# DAU_Kupplung_3phasig_V1_3.net
KiCad netlist of a schematic drawn in EAGLE
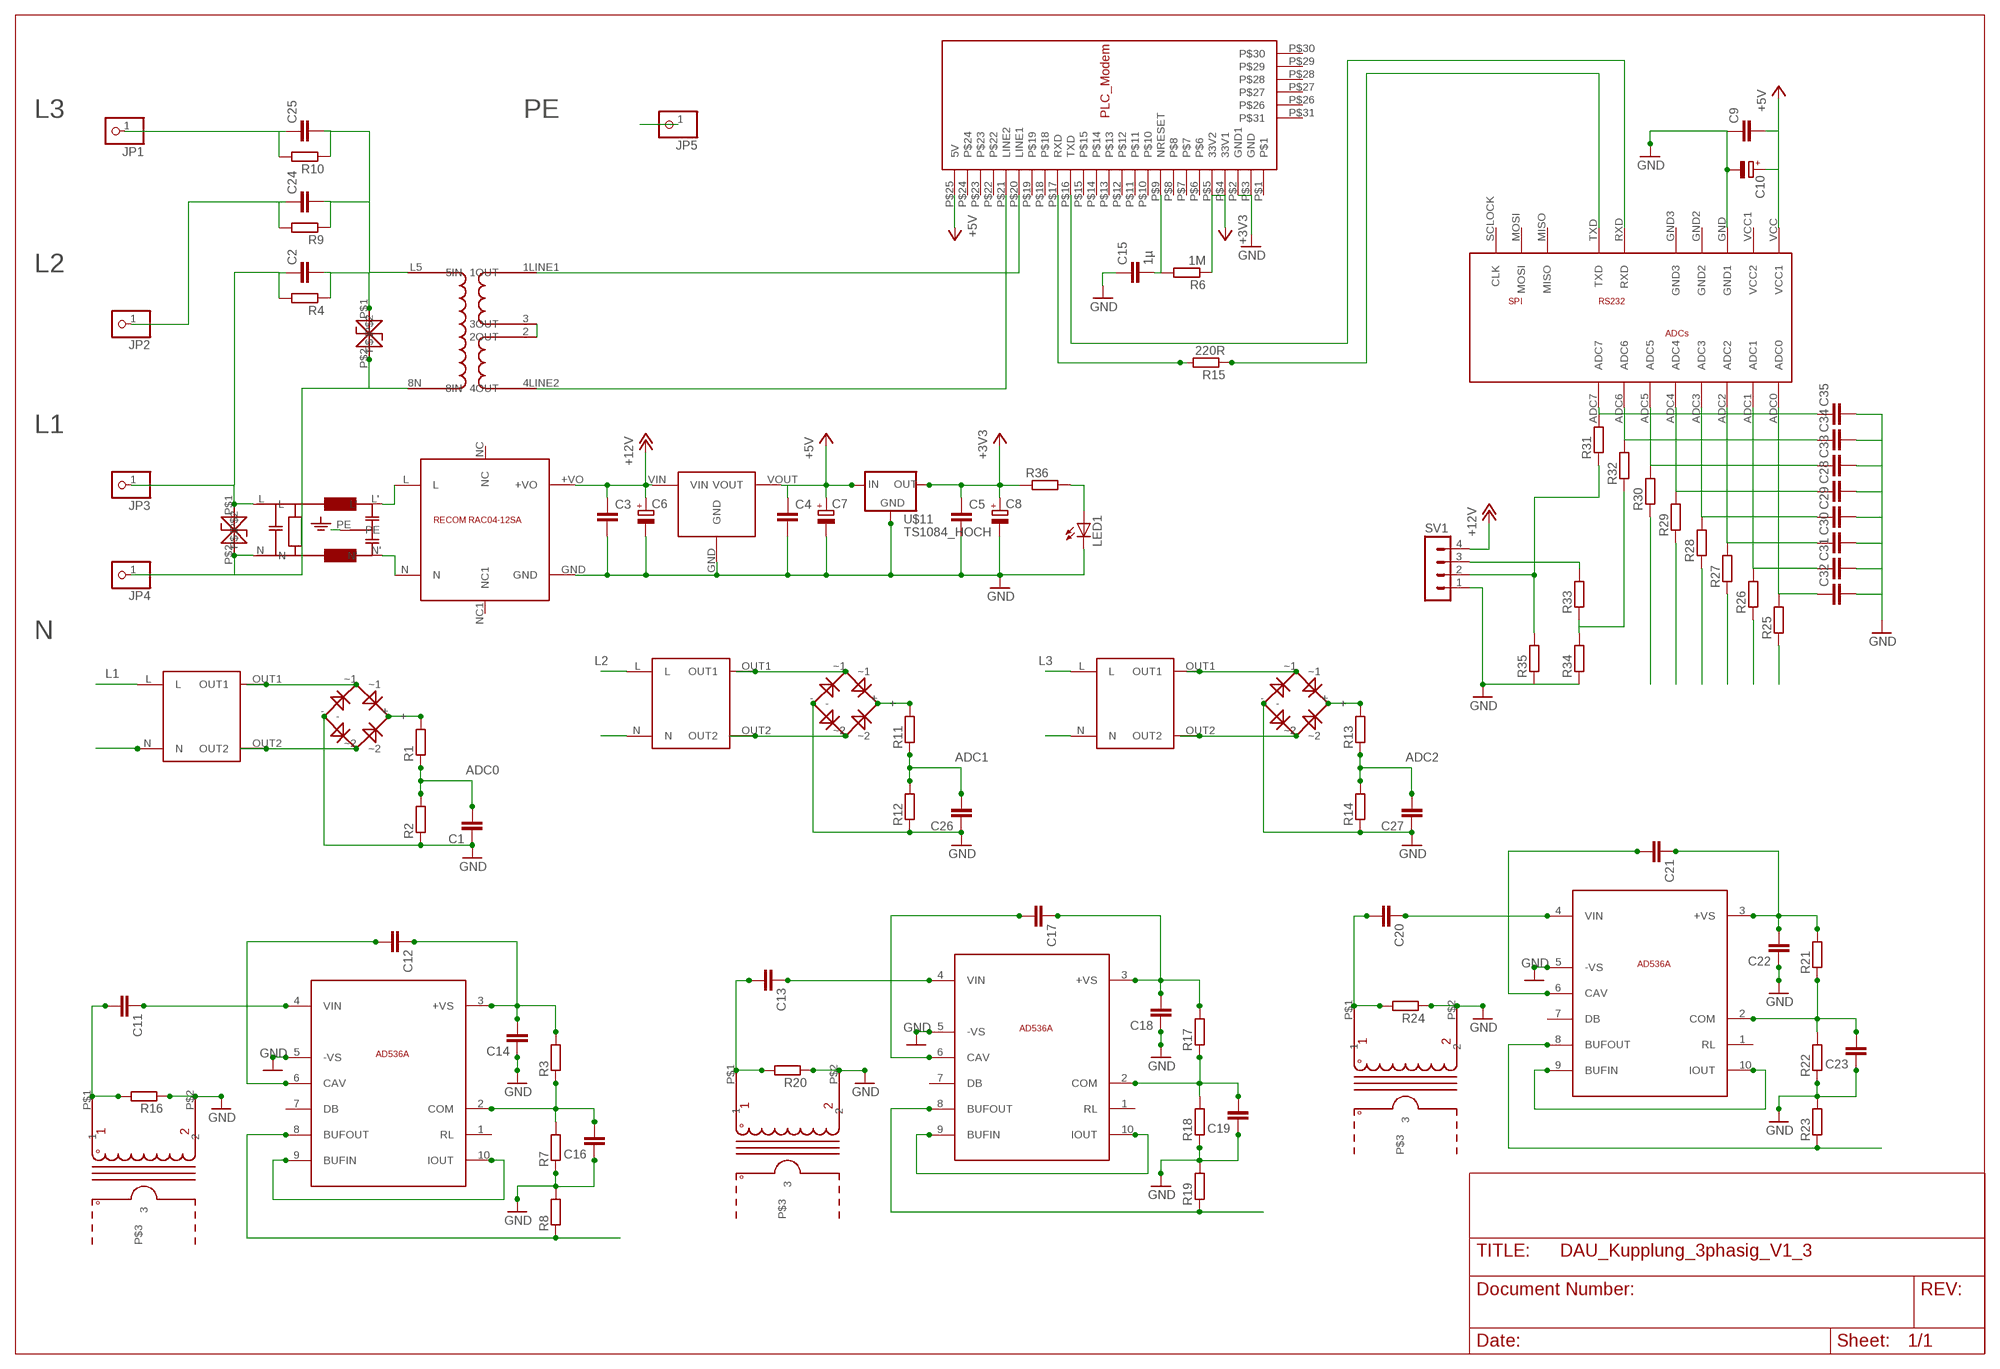
[diagram p0: schematic, sheet 1]

(export (version "E")
  (design (tool "Eeschema 10.0.6"))
  (components
    (comp (ref "C1")
      (value "C2,5-3")
      (footprint "eagle-import:C2.5-3")
      (libsource (lib "eagle-import") (part "C2,5-3"))
    )
    (comp (ref "C2")
      (value "C-EU225-087X268")
      (footprint "eagle-import:C225-087X268")
      (libsource (lib "eagle-import") (part "resistor_C-EU225-087X268"))
    )
    (comp (ref "C3")
      (value "C-EU025-040X050")
      (footprint "eagle-import:C025-040X050")
      (libsource (lib "eagle-import") (part "resistor_C-EU025-040X050"))
    )
    (comp (ref "C4")
      (value "C-EU025-040X050")
      (footprint "eagle-import:C025-040X050")
      (libsource (lib "eagle-import") (part "resistor_C-EU025-040X050"))
    )
    (comp (ref "C5")
      (value "C-EU025-040X050")
      (footprint "eagle-import:C025-040X050")
      (libsource (lib "eagle-import") (part "resistor_C-EU025-040X050"))
    )
    (comp (ref "C6")
      (value "CPOL-EUE2.5-6")
      (footprint "eagle-import:E2,5-6")
      (libsource (lib "eagle-import") (part "resistor_CPOL-EUE2.5-6"))
    )
    (comp (ref "C7")
      (value "CPOL-EUE2.5-6")
      (footprint "eagle-import:E2,5-6")
      (libsource (lib "eagle-import") (part "resistor_CPOL-EUE2.5-6"))
    )
    (comp (ref "C8")
      (value "CPOL-EUE2.5-6")
      (footprint "eagle-import:E2,5-6")
      (libsource (lib "eagle-import") (part "resistor_CPOL-EUE2.5-6"))
    )
    (comp (ref "C9")
      (value "C-EU025-040X050")
      (footprint "eagle-import:C025-040X050")
      (libsource (lib "eagle-import") (part "C-EU025-040X050"))
    )
    (comp (ref "C10")
      (value "CPOL-EUE2,5-6E")
      (footprint "eagle-import:E2,5-6E")
      (libsource (lib "eagle-import") (part "CPOL-EUE2,5-6E"))
    )
    (comp (ref "C11")
      (value "C2,5-3")
      (footprint "eagle-import:C2.5-3")
      (libsource (lib "eagle-import") (part "C2,5-3"))
    )
    (comp (ref "C12")
      (value "C2,5-3")
      (footprint "eagle-import:C2.5-3")
      (libsource (lib "eagle-import") (part "C2,5-3"))
    )
    (comp (ref "C13")
      (value "C2,5-3")
      (footprint "eagle-import:C2.5-3")
      (libsource (lib "eagle-import") (part "C2,5-3"))
    )
    (comp (ref "C14")
      (value "C2,5-3")
      (footprint "eagle-import:C2.5-3")
      (libsource (lib "eagle-import") (part "C2,5-3"))
    )
    (comp (ref "C15")
      (value "1µ")
      (footprint "eagle-import:C025-040X050")
      (libsource (lib "eagle-import") (part "resistor_C-EU025-040X050"))
    )
    (comp (ref "C16")
      (value "C2,5-3")
      (footprint "eagle-import:C2.5-3")
      (libsource (lib "eagle-import") (part "C2,5-3"))
    )
    (comp (ref "C17")
      (value "C2,5-3")
      (footprint "eagle-import:C2.5-3")
      (libsource (lib "eagle-import") (part "C2,5-3"))
    )
    (comp (ref "C18")
      (value "C2,5-3")
      (footprint "eagle-import:C2.5-3")
      (libsource (lib "eagle-import") (part "C2,5-3"))
    )
    (comp (ref "C19")
      (value "C2,5-3")
      (footprint "eagle-import:C2.5-3")
      (libsource (lib "eagle-import") (part "C2,5-3"))
    )
    (comp (ref "C20")
      (value "C2,5-3")
      (footprint "eagle-import:C2.5-3")
      (libsource (lib "eagle-import") (part "C2,5-3"))
    )
    (comp (ref "C21")
      (value "C2,5-3")
      (footprint "eagle-import:C2.5-3")
      (libsource (lib "eagle-import") (part "C2,5-3"))
    )
    (comp (ref "C22")
      (value "C2,5-3")
      (footprint "eagle-import:C2.5-3")
      (libsource (lib "eagle-import") (part "C2,5-3"))
    )
    (comp (ref "C23")
      (value "C2,5-3")
      (footprint "eagle-import:C2.5-3")
      (libsource (lib "eagle-import") (part "C2,5-3"))
    )
    (comp (ref "C24")
      (value "C-EU225-087X268")
      (footprint "eagle-import:C225-087X268")
      (libsource (lib "eagle-import") (part "resistor_C-EU225-087X268"))
    )
    (comp (ref "C25")
      (value "C-EU225-087X268")
      (footprint "eagle-import:C225-087X268")
      (libsource (lib "eagle-import") (part "resistor_C-EU225-087X268"))
    )
    (comp (ref "C26")
      (value "C2,5-3")
      (footprint "eagle-import:C2.5-3")
      (libsource (lib "eagle-import") (part "C2,5-3"))
    )
    (comp (ref "C27")
      (value "C2,5-3")
      (footprint "eagle-import:C2.5-3")
      (libsource (lib "eagle-import") (part "C2,5-3"))
    )
    (comp (ref "C28")
      (value "C-EUC0805K")
      (footprint "eagle-import:C0805K")
      (libsource (lib "eagle-import") (part "resistor_C-EUC0805K"))
    )
    (comp (ref "C29")
      (value "C-EUC0805K")
      (footprint "eagle-import:C0805K")
      (libsource (lib "eagle-import") (part "resistor_C-EUC0805K"))
    )
    (comp (ref "C30")
      (value "C-EUC0805K")
      (footprint "eagle-import:C0805K")
      (libsource (lib "eagle-import") (part "resistor_C-EUC0805K"))
    )
    (comp (ref "C31")
      (value "C-EUC0805K")
      (footprint "eagle-import:C0805K")
      (libsource (lib "eagle-import") (part "resistor_C-EUC0805K"))
    )
    (comp (ref "C32")
      (value "C-EUC0805K")
      (footprint "eagle-import:C0805K")
      (libsource (lib "eagle-import") (part "resistor_C-EUC0805K"))
    )
    (comp (ref "C33")
      (value "C-EUC0805K")
      (footprint "eagle-import:C0805K")
      (libsource (lib "eagle-import") (part "resistor_C-EUC0805K"))
    )
    (comp (ref "C34")
      (value "C-EUC0805K")
      (footprint "eagle-import:C0805K")
      (libsource (lib "eagle-import") (part "resistor_C-EUC0805K"))
    )
    (comp (ref "C35")
      (value "C-EUC0805K")
      (footprint "eagle-import:C0805K")
      (libsource (lib "eagle-import") (part "resistor_C-EUC0805K"))
    )
    (comp (ref "JP1")
      (value "PINHD-1X1")
      (footprint "eagle-import:1X01")
      (libsource (lib "eagle-import") (part "PINHD-1X1"))
    )
    (comp (ref "JP2")
      (value "PINHD-1X1")
      (footprint "eagle-import:1X01")
      (libsource (lib "eagle-import") (part "PINHD-1X1"))
    )
    (comp (ref "JP3")
      (value "PINHD-1X1")
      (footprint "eagle-import:1X01")
      (libsource (lib "eagle-import") (part "PINHD-1X1"))
    )
    (comp (ref "JP4")
      (value "PINHD-1X1")
      (footprint "eagle-import:1X01")
      (libsource (lib "eagle-import") (part "PINHD-1X1"))
    )
    (comp (ref "JP5")
      (value "PINHD-1X1")
      (footprint "eagle-import:1X01")
      (libsource (lib "eagle-import") (part "PINHD-1X1"))
    )
    (comp (ref "LED1")
      (value "LEDSQR2X5")
      (footprint "eagle-import:LED2X5")
      (libsource (lib "eagle-import") (part "LEDSQR2X5"))
    )
    (comp (ref "R1")
      (value "R-EU_0204/7")
      (footprint "eagle-import:0204_7")
      (libsource (lib "eagle-import") (part "R-EU_0204/7"))
    )
    (comp (ref "R2")
      (value "R-EU_0204/7")
      (footprint "eagle-import:0204_7")
      (libsource (lib "eagle-import") (part "R-EU_0204/7"))
    )
    (comp (ref "R3")
      (value "R-EU_0204/7")
      (footprint "eagle-import:0204_7")
      (libsource (lib "eagle-import") (part "R-EU_0204/7"))
    )
    (comp (ref "R4")
      (value "R-EU_0204/7")
      (footprint "eagle-import:0204_7")
      (libsource (lib "eagle-import") (part "R-EU_0204/7"))
    )
    (comp (ref "R6")
      (value "1M")
      (footprint "eagle-import:0204_7")
      (libsource (lib "eagle-import") (part "R-EU_0204/7"))
    )
    (comp (ref "R7")
      (value "R-EU_0204/7")
      (footprint "eagle-import:0204_7")
      (libsource (lib "eagle-import") (part "R-EU_0204/7"))
    )
    (comp (ref "R8")
      (value "R-EU_0204/7")
      (footprint "eagle-import:0204_7")
      (libsource (lib "eagle-import") (part "R-EU_0204/7"))
    )
    (comp (ref "R9")
      (value "R-EU_0204/7")
      (footprint "eagle-import:0204_7")
      (libsource (lib "eagle-import") (part "R-EU_0204/7"))
    )
    (comp (ref "R10")
      (value "R-EU_0204/7")
      (footprint "eagle-import:0204_7")
      (libsource (lib "eagle-import") (part "R-EU_0204/7"))
    )
    (comp (ref "R11")
      (value "R-EU_0204/7")
      (footprint "eagle-import:0204_7")
      (libsource (lib "eagle-import") (part "R-EU_0204/7"))
    )
    (comp (ref "R12")
      (value "R-EU_0204/7")
      (footprint "eagle-import:0204_7")
      (libsource (lib "eagle-import") (part "R-EU_0204/7"))
    )
    (comp (ref "R13")
      (value "R-EU_0204/7")
      (footprint "eagle-import:0204_7")
      (libsource (lib "eagle-import") (part "R-EU_0204/7"))
    )
    (comp (ref "R14")
      (value "R-EU_0204/7")
      (footprint "eagle-import:0204_7")
      (libsource (lib "eagle-import") (part "R-EU_0204/7"))
    )
    (comp (ref "R15")
      (value "220R")
      (footprint "eagle-import:0204_7")
      (libsource (lib "eagle-import") (part "R-EU_0204/7"))
    )
    (comp (ref "R16")
      (value "R-EU_0204/7")
      (footprint "eagle-import:0204_7")
      (libsource (lib "eagle-import") (part "R-EU_0204/7"))
    )
    (comp (ref "R17")
      (value "R-EU_0204/7")
      (footprint "eagle-import:0204_7")
      (libsource (lib "eagle-import") (part "R-EU_0204/7"))
    )
    (comp (ref "R18")
      (value "R-EU_0204/7")
      (footprint "eagle-import:0204_7")
      (libsource (lib "eagle-import") (part "R-EU_0204/7"))
    )
    (comp (ref "R19")
      (value "R-EU_0204/7")
      (footprint "eagle-import:0204_7")
      (libsource (lib "eagle-import") (part "R-EU_0204/7"))
    )
    (comp (ref "R20")
      (value "R-EU_0204/7")
      (footprint "eagle-import:0204_7")
      (libsource (lib "eagle-import") (part "R-EU_0204/7"))
    )
    (comp (ref "R21")
      (value "R-EU_0204/7")
      (footprint "eagle-import:0204_7")
      (libsource (lib "eagle-import") (part "R-EU_0204/7"))
    )
    (comp (ref "R22")
      (value "R-EU_0204/7")
      (footprint "eagle-import:0204_7")
      (libsource (lib "eagle-import") (part "R-EU_0204/7"))
    )
    (comp (ref "R23")
      (value "R-EU_0204/7")
      (footprint "eagle-import:0204_7")
      (libsource (lib "eagle-import") (part "R-EU_0204/7"))
    )
    (comp (ref "R24")
      (value "R-EU_0204/7")
      (footprint "eagle-import:0204_7")
      (libsource (lib "eagle-import") (part "R-EU_0204/7"))
    )
    (comp (ref "R25")
      (value "R-EU_R0805")
      (footprint "eagle-import:R0805")
      (libsource (lib "eagle-import") (part "R-EU_R0805"))
    )
    (comp (ref "R26")
      (value "R-EU_R0805")
      (footprint "eagle-import:R0805")
      (libsource (lib "eagle-import") (part "R-EU_R0805"))
    )
    (comp (ref "R27")
      (value "R-EU_R0805")
      (footprint "eagle-import:R0805")
      (libsource (lib "eagle-import") (part "R-EU_R0805"))
    )
    (comp (ref "R28")
      (value "R-EU_R0805")
      (footprint "eagle-import:R0805")
      (libsource (lib "eagle-import") (part "R-EU_R0805"))
    )
    (comp (ref "R29")
      (value "R-EU_R0805")
      (footprint "eagle-import:R0805")
      (libsource (lib "eagle-import") (part "R-EU_R0805"))
    )
    (comp (ref "R30")
      (value "R-EU_R0805")
      (footprint "eagle-import:R0805")
      (libsource (lib "eagle-import") (part "R-EU_R0805"))
    )
    (comp (ref "R31")
      (value "R-EU_R0805")
      (footprint "eagle-import:R0805")
      (libsource (lib "eagle-import") (part "R-EU_R0805"))
    )
    (comp (ref "R32")
      (value "R-EU_R0805")
      (footprint "eagle-import:R0805")
      (libsource (lib "eagle-import") (part "R-EU_R0805"))
    )
    (comp (ref "R33")
      (value "R-EU_R0805")
      (footprint "eagle-import:R0805")
      (libsource (lib "eagle-import") (part "R-EU_R0805"))
    )
    (comp (ref "R34")
      (value "R-EU_R0805")
      (footprint "eagle-import:R0805")
      (libsource (lib "eagle-import") (part "R-EU_R0805"))
    )
    (comp (ref "R35")
      (value "R-EU_R0805")
      (footprint "eagle-import:R0805")
      (libsource (lib "eagle-import") (part "R-EU_R0805"))
    )
    (comp (ref "R36")
      (value "R-EU_R0805")
      (footprint "eagle-import:R0805")
      (libsource (lib "eagle-import") (part "R-EU_R0805"))
    )
    (comp (ref "SV1")
      (value "MA04-1")
      (footprint "eagle-import:MA04-1")
      (libsource (lib "eagle-import") (part "MA04-1"))
    )
    (comp (ref "TSV1")
      (value "TSV")
      (footprint "eagle-import:TSV")
      (libsource (lib "eagle-import") (part "TSV"))
    )
    (comp (ref "TSV2")
      (value "TSV")
      (footprint "eagle-import:TSV")
      (libsource (lib "eagle-import") (part "TSV"))
    )
    (comp (ref "U$1")
      (value "RECOM_RAC04_12SA")
      (footprint "eagle-import:RAC04_12SA")
      (libsource (lib "eagle-import") (part "RECOM_RAC04_12SA"))
    )
    (comp (ref "U$2")
      (value "SICHERHEITSTRAFO")
      (footprint "eagle-import:TRAFO_0,35VA")
      (libsource (lib "eagle-import") (part "SICHERHEITSTRAFO"))
    )
    (comp (ref "U$3")
      (value "ADUC831_MINIMUM")
      (footprint "eagle-import:ADUC_MINIMUM")
      (libsource (lib "eagle-import") (part "ADUC831_MINIMUM"))
    )
    (comp (ref "U$4")
      (value "MODEMSTECKER")
      (footprint "eagle-import:MODEM_FUSS")
      (libsource (lib "eagle-import") (part "MODEMSTECKER"))
    )
    (comp (ref "U$5")
      (value "PLC_UEBERTRAGER_V2")
      (footprint "eagle-import:PLC-UEBERTRAGER_V2")
      (libsource (lib "eagle-import") (part "PLC_UEBERTRAGER_V2"))
    )
    (comp (ref "U$6")
      (value "AC1010")
      (footprint "eagle-import:AC1010")
      (libsource (lib "eagle-import") (part "AC1010"))
    )
    (comp (ref "U$7")
      (value "AC1010")
      (footprint "eagle-import:AC1010")
      (libsource (lib "eagle-import") (part "AC1010"))
    )
    (comp (ref "U$8")
      (value "RECTIFIER")
      (footprint "eagle-import:RECTIFIER")
      (libsource (lib "eagle-import") (part "RECTIFIER"))
    )
    (comp (ref "U$10")
      (value "RECOM_785_05")
      (footprint "eagle-import:RECOM785X")
      (libsource (lib "eagle-import") (part "RECOM_785_05"))
    )
    (comp (ref "U$11")
      (value "TS1084_HOCH")
      (footprint "eagle-import:TS1084_HOCH")
      (libsource (lib "eagle-import") (part "TS1084_HOCH"))
    )
    (comp (ref "U$12")
      (value "AD536")
      (footprint "eagle-import:TO100_10PIN")
      (libsource (lib "eagle-import") (part "AD536"))
    )
    (comp (ref "U$13")
      (value "AD536")
      (footprint "eagle-import:TO100_10PIN")
      (libsource (lib "eagle-import") (part "AD536"))
    )
    (comp (ref "U$14")
      (value "AC1010")
      (footprint "eagle-import:AC1010")
      (libsource (lib "eagle-import") (part "AC1010"))
    )
    (comp (ref "U$15")
      (value "AD536")
      (footprint "eagle-import:TO100_10PIN")
      (libsource (lib "eagle-import") (part "AD536"))
    )
    (comp (ref "U$16")
      (value "SICHERHEITSTRAFO")
      (footprint "eagle-import:TRAFO_0,35VA")
      (libsource (lib "eagle-import") (part "SICHERHEITSTRAFO"))
    )
    (comp (ref "U$17")
      (value "RECTIFIER")
      (footprint "eagle-import:RECTIFIER")
      (libsource (lib "eagle-import") (part "RECTIFIER"))
    )
    (comp (ref "U$18")
      (value "SICHERHEITSTRAFO")
      (footprint "eagle-import:TRAFO_0,35VA")
      (libsource (lib "eagle-import") (part "SICHERHEITSTRAFO"))
    )
    (comp (ref "U$19")
      (value "RECTIFIER")
      (footprint "eagle-import:RECTIFIER")
      (libsource (lib "eagle-import") (part "RECTIFIER"))
    )
    (comp (ref "U$20")
      (value "NETZFILTER_05_A")
      (footprint "eagle-import:NETZFILTER")
      (libsource (lib "eagle-import") (part "NETZFILTER_05_A"))
    )
  )
  (nets
    (net (code "1") (name "+3V3") (class "Default")
      (node (ref "C5") (pin "1") (pinfunction "1_1") (pintype "passive"))
      (node (ref "C8") (pin "+") (pinfunction "+_+") (pintype "passive"))
      (node (ref "R36") (pin "1") (pinfunction "1_1") (pintype "passive"))
      (node (ref "R6") (pin "1") (pinfunction "1_1") (pintype "passive"))
      (node (ref "U$11") (pin "OUT") (pinfunction "OUT_OUT") (pintype "passive"))
      (node (ref "U$4") (pin "P$4") (pinfunction "33V1_P$4") (pintype "bidirectional"))
      (node (ref "U$4") (pin "P$5") (pinfunction "33V2_P$5") (pintype "bidirectional"))
    )
    (net (code "2") (name "+5V") (class "Default")
      (node (ref "C10") (pin "+") (pinfunction "+_+") (pintype "passive"))
      (node (ref "C4") (pin "1") (pinfunction "1_1") (pintype "passive"))
      (node (ref "C7") (pin "+") (pinfunction "+_+") (pintype "passive"))
      (node (ref "C9") (pin "2") (pinfunction "2_2") (pintype "passive"))
      (node (ref "U$10") (pin "VOUT") (pinfunction "VOUT_VOUT") (pintype "bidirectional"))
      (node (ref "U$11") (pin "IN") (pinfunction "IN_IN") (pintype "input"))
      (node (ref "U$3") (pin "VCC") (pinfunction "VCC1_VCC") (pintype "bidirectional"))
      (node (ref "U$4") (pin "P$25") (pinfunction "5V_P$25") (pintype "bidirectional"))
    )
    (net (code "3") (name "+12V") (class "Default")
      (node (ref "C3") (pin "1") (pinfunction "1_1") (pintype "passive"))
      (node (ref "C6") (pin "+") (pinfunction "+_+") (pintype "passive"))
      (node (ref "SV1") (pin "4") (pinfunction "4_4") (pintype "passive"))
      (node (ref "U$1") (pin "+VO") (pinfunction "+VO_+VO") (pintype "bidirectional"))
      (node (ref "U$10") (pin "VIN") (pinfunction "VIN_VIN") (pintype "bidirectional"))
    )
    (net (code "4") (name "/I1") (class "Default")
      (node (ref "R28") (pin "1") (pinfunction "1_1") (pintype "passive"))
      (node (ref "R8") (pin "1") (pinfunction "1_1") (pintype "passive"))
      (node (ref "U$13") (pin "8") (pinfunction "BUFOUT_8") (pintype "bidirectional"))
    )
    (net (code "5") (name "/I2") (class "Default")
      (node (ref "R19") (pin "1") (pinfunction "1_1") (pintype "passive"))
      (node (ref "R29") (pin "1") (pinfunction "1_1") (pintype "passive"))
      (node (ref "U$12") (pin "8") (pinfunction "BUFOUT_8") (pintype "bidirectional"))
    )
    (net (code "6") (name "/I3") (class "Default")
      (node (ref "R23") (pin "1") (pinfunction "1_1") (pintype "passive"))
      (node (ref "R30") (pin "1") (pinfunction "1_1") (pintype "passive"))
      (node (ref "U$15") (pin "8") (pinfunction "BUFOUT_8") (pintype "bidirectional"))
    )
    (net (code "7") (name "/L1") (class "Default")
      (node (ref "C2") (pin "1") (pinfunction "1_1") (pintype "passive"))
      (node (ref "JP3") (pin "1") (pinfunction "1_1") (pintype "passive"))
      (node (ref "R4") (pin "2") (pinfunction "2_2") (pintype "passive"))
      (node (ref "TSV1") (pin "P$1") (pinfunction "P$1_P$1") (pintype "bidirectional"))
      (node (ref "U$2") (pin "L") (pinfunction "L_L") (pintype "bidirectional"))
      (node (ref "U$20") (pin "L") (pinfunction "L_L") (pintype "bidirectional"))
    )
    (net (code "8") (name "/L2") (class "Default")
      (node (ref "C24") (pin "1") (pinfunction "1_1") (pintype "passive"))
      (node (ref "JP2") (pin "1") (pinfunction "1_1") (pintype "passive"))
      (node (ref "R9") (pin "2") (pinfunction "2_2") (pintype "passive"))
      (node (ref "U$16") (pin "L") (pinfunction "L_L") (pintype "bidirectional"))
    )
    (net (code "9") (name "/L3") (class "Default")
      (node (ref "C25") (pin "1") (pinfunction "1_1") (pintype "passive"))
      (node (ref "JP1") (pin "1") (pinfunction "1_1") (pintype "passive"))
      (node (ref "R10") (pin "2") (pinfunction "2_2") (pintype "passive"))
      (node (ref "U$18") (pin "L") (pinfunction "L_L") (pintype "bidirectional"))
    )
    (net (code "10") (name "/N") (class "Default")
      (node (ref "JP4") (pin "1") (pinfunction "1_1") (pintype "passive"))
      (node (ref "TSV1") (pin "P$2") (pinfunction "P$2_P$2") (pintype "bidirectional"))
      (node (ref "TSV2") (pin "P$2") (pinfunction "P$2_P$2") (pintype "bidirectional"))
      (node (ref "U$16") (pin "N") (pinfunction "N_N") (pintype "bidirectional"))
      (node (ref "U$18") (pin "N") (pinfunction "N_N") (pintype "bidirectional"))
      (node (ref "U$2") (pin "N") (pinfunction "N_N") (pintype "bidirectional"))
      (node (ref "U$20") (pin "N") (pinfunction "N_N") (pintype "bidirectional"))
      (node (ref "U$5") (pin "8N") (pinfunction "8IN_8N") (pintype "input"))
    )
    (net (code "11") (name "/PE") (class "Default")
      (node (ref "JP5") (pin "1") (pinfunction "1_1") (pintype "passive"))
      (node (ref "U$20") (pin "PE") (pinfunction "PE_PE") (pintype "input"))
    )
    (net (code "12") (name "/U1") (class "Default")
      (node (ref "C1") (pin "2") (pinfunction "2_2") (pintype "passive"))
      (node (ref "R1") (pin "1") (pinfunction "1_1") (pintype "passive"))
      (node (ref "R2") (pin "2") (pinfunction "2_2") (pintype "passive"))
      (node (ref "R25") (pin "1") (pinfunction "1_1") (pintype "passive"))
    )
    (net (code "13") (name "/U2") (class "Default")
      (node (ref "C26") (pin "2") (pinfunction "2_2") (pintype "passive"))
      (node (ref "R11") (pin "1") (pinfunction "1_1") (pintype "passive"))
      (node (ref "R12") (pin "2") (pinfunction "2_2") (pintype "passive"))
      (node (ref "R26") (pin "1") (pinfunction "1_1") (pintype "passive"))
    )
    (net (code "14") (name "/U3") (class "Default")
      (node (ref "C27") (pin "2") (pinfunction "2_2") (pintype "passive"))
      (node (ref "R13") (pin "1") (pinfunction "1_1") (pintype "passive"))
      (node (ref "R14") (pin "2") (pinfunction "2_2") (pintype "passive"))
      (node (ref "R27") (pin "1") (pinfunction "1_1") (pintype "passive"))
    )
    (net (code "15") (name "GND") (class "Default")
      (node (ref "C1") (pin "1") (pinfunction "1_1") (pintype "passive"))
      (node (ref "C10") (pin "-") (pinfunction "-_-") (pintype "passive"))
      (node (ref "C14") (pin "1") (pinfunction "1_1") (pintype "passive"))
      (node (ref "C15") (pin "1") (pinfunction "1_1") (pintype "passive"))
      (node (ref "C16") (pin "1") (pinfunction "1_1") (pintype "passive"))
      (node (ref "C18") (pin "1") (pinfunction "1_1") (pintype "passive"))
      (node (ref "C19") (pin "1") (pinfunction "1_1") (pintype "passive"))
      (node (ref "C22") (pin "1") (pinfunction "1_1") (pintype "passive"))
      (node (ref "C23") (pin "1") (pinfunction "1_1") (pintype "passive"))
      (node (ref "C26") (pin "1") (pinfunction "1_1") (pintype "passive"))
      (node (ref "C27") (pin "1") (pinfunction "1_1") (pintype "passive"))
      (node (ref "C28") (pin "2") (pinfunction "2_2") (pintype "passive"))
      (node (ref "C29") (pin "2") (pinfunction "2_2") (pintype "passive"))
      (node (ref "C3") (pin "2") (pinfunction "2_2") (pintype "passive"))
      (node (ref "C30") (pin "2") (pinfunction "2_2") (pintype "passive"))
      (node (ref "C31") (pin "2") (pinfunction "2_2") (pintype "passive"))
      (node (ref "C32") (pin "2") (pinfunction "2_2") (pintype "passive"))
      (node (ref "C33") (pin "2") (pinfunction "2_2") (pintype "passive"))
      (node (ref "C34") (pin "2") (pinfunction "2_2") (pintype "passive"))
      (node (ref "C35") (pin "2") (pinfunction "2_2") (pintype "passive"))
      (node (ref "C4") (pin "2") (pinfunction "2_2") (pintype "passive"))
      (node (ref "C5") (pin "2") (pinfunction "2_2") (pintype "passive"))
      (node (ref "C6") (pin "-") (pinfunction "-_-") (pintype "passive"))
      (node (ref "C7") (pin "-") (pinfunction "-_-") (pintype "passive"))
      (node (ref "C8") (pin "-") (pinfunction "-_-") (pintype "passive"))
      (node (ref "C9") (pin "1") (pinfunction "1_1") (pintype "passive"))
      (node (ref "LED1") (pin "K") (pinfunction "C_K") (pintype "passive"))
      (node (ref "R12") (pin "1") (pinfunction "1_1") (pintype "passive"))
      (node (ref "R14") (pin "1") (pinfunction "1_1") (pintype "passive"))
      (node (ref "R16") (pin "1") (pinfunction "1_1") (pintype "passive"))
      (node (ref "R18") (pin "1") (pinfunction "1_1") (pintype "passive"))
      (node (ref "R19") (pin "2") (pinfunction "2_2") (pintype "passive"))
      (node (ref "R2") (pin "1") (pinfunction "1_1") (pintype "passive"))
      (node (ref "R20") (pin "1") (pinfunction "1_1") (pintype "passive"))
      (node (ref "R22") (pin "1") (pinfunction "1_1") (pintype "passive"))
      (node (ref "R23") (pin "2") (pinfunction "2_2") (pintype "passive"))
      (node (ref "R24") (pin "1") (pinfunction "1_1") (pintype "passive"))
      (node (ref "R34") (pin "1") (pinfunction "1_1") (pintype "passive"))
      (node (ref "R35") (pin "1") (pinfunction "1_1") (pintype "passive"))
      (node (ref "R7") (pin "1") (pinfunction "1_1") (pintype "passive"))
      (node (ref "R8") (pin "2") (pinfunction "2_2") (pintype "passive"))
      (node (ref "SV1") (pin "1") (pinfunction "1_1") (pintype "passive"))
      (node (ref "U$1") (pin "GND") (pinfunction "GND_GND") (pintype "bidirectional"))
      (node (ref "U$10") (pin "GND") (pinfunction "GND_GND") (pintype "bidirectional"))
      (node (ref "U$11") (pin "GND") (pinfunction "GND_GND") (pintype "input"))
      (node (ref "U$12") (pin "5") (pinfunction "-VS_5") (pintype "bidirectional"))
      (node (ref "U$13") (pin "5") (pinfunction "-VS_5") (pintype "bidirectional"))
      (node (ref "U$14") (pin "P$2") (pinfunction "2_P$2") (pintype "output"))
      (node (ref "U$15") (pin "5") (pinfunction "-VS_5") (pintype "bidirectional"))
      (node (ref "U$17") (pin "-") (pinfunction "-_-") (pintype "bidirectional"))
      (node (ref "U$19") (pin "-") (pinfunction "-_-") (pintype "bidirectional"))
      (node (ref "U$3") (pin "GND") (pinfunction "GND1_GND") (pintype "bidirectional"))
      (node (ref "U$4") (pin "P$2") (pinfunction "GND1_P$2") (pintype "bidirectional"))
      (node (ref "U$4") (pin "P$3") (pinfunction "GND_P$3") (pintype "bidirectional"))
      (node (ref "U$6") (pin "P$2") (pinfunction "2_P$2") (pintype "output"))
      (node (ref "U$7") (pin "P$2") (pinfunction "2_P$2") (pintype "output"))
      (node (ref "U$8") (pin "-") (pinfunction "-_-") (pintype "bidirectional"))
    )
    (net (code "16") (name "Net-(C28-Pad1)") (class "Default")
      (node (ref "C28") (pin "1") (pinfunction "1_1") (pintype "passive"))
      (node (ref "R29") (pin "2") (pinfunction "2_2") (pintype "passive"))
      (node (ref "U$3") (pin "ADC4") (pinfunction "ADC4_ADC4") (pintype "bidirectional"))
    )
    (net (code "17") (name "Net-(C29-Pad1)") (class "Default")
      (node (ref "C29") (pin "1") (pinfunction "1_1") (pintype "passive"))
      (node (ref "R28") (pin "2") (pinfunction "2_2") (pintype "passive"))
      (node (ref "U$3") (pin "ADC3") (pinfunction "ADC3_ADC3") (pintype "bidirectional"))
    )
    (net (code "18") (name "Net-(C30-Pad1)") (class "Default")
      (node (ref "C30") (pin "1") (pinfunction "1_1") (pintype "passive"))
      (node (ref "R27") (pin "2") (pinfunction "2_2") (pintype "passive"))
      (node (ref "U$3") (pin "ADC2") (pinfunction "ADC2_ADC2") (pintype "bidirectional"))
    )
    (net (code "19") (name "Net-(C31-Pad1)") (class "Default")
      (node (ref "C31") (pin "1") (pinfunction "1_1") (pintype "passive"))
      (node (ref "R26") (pin "2") (pinfunction "2_2") (pintype "passive"))
      (node (ref "U$3") (pin "ADC1") (pinfunction "ADC1_ADC1") (pintype "bidirectional"))
    )
    (net (code "20") (name "Net-(C32-Pad1)") (class "Default")
      (node (ref "C32") (pin "1") (pinfunction "1_1") (pintype "passive"))
      (node (ref "R25") (pin "2") (pinfunction "2_2") (pintype "passive"))
      (node (ref "U$3") (pin "ADC0") (pinfunction "ADC0_ADC0") (pintype "bidirectional"))
    )
    (net (code "21") (name "Net-(C33-Pad1)") (class "Default")
      (node (ref "C33") (pin "1") (pinfunction "1_1") (pintype "passive"))
      (node (ref "R30") (pin "2") (pinfunction "2_2") (pintype "passive"))
      (node (ref "U$3") (pin "ADC5") (pinfunction "ADC5_ADC5") (pintype "bidirectional"))
    )
    (net (code "22") (name "Net-(C34-Pad1)") (class "Default")
      (node (ref "C34") (pin "1") (pinfunction "1_1") (pintype "passive"))
      (node (ref "R32") (pin "2") (pinfunction "2_2") (pintype "passive"))
      (node (ref "U$3") (pin "ADC6") (pinfunction "ADC6_ADC6") (pintype "bidirectional"))
    )
    (net (code "23") (name "Net-(C35-Pad1)") (class "Default")
      (node (ref "C35") (pin "1") (pinfunction "1_1") (pintype "passive"))
      (node (ref "R31") (pin "2") (pinfunction "2_2") (pintype "passive"))
      (node (ref "U$3") (pin "ADC7") (pinfunction "ADC7_ADC7") (pintype "bidirectional"))
    )
    (net (code "24") (name "Net-(LED1-PadA)") (class "Default")
      (node (ref "LED1") (pin "A") (pinfunction "A_A") (pintype "passive"))
      (node (ref "R36") (pin "2") (pinfunction "2_2") (pintype "passive"))
    )
    (net (code "25") (name "Net-(R1-Pad2)") (class "Default")
      (node (ref "R1") (pin "2") (pinfunction "2_2") (pintype "passive"))
      (node (ref "U$8") (pin "+") (pinfunction "+_+") (pintype "bidirectional"))
    )
    (net (code "26") (name "Net-(R11-Pad2)") (class "Default")
      (node (ref "R11") (pin "2") (pinfunction "2_2") (pintype "passive"))
      (node (ref "U$17") (pin "+") (pinfunction "+_+") (pintype "bidirectional"))
    )
    (net (code "27") (name "Net-(R13-Pad2)") (class "Default")
      (node (ref "R13") (pin "2") (pinfunction "2_2") (pintype "passive"))
      (node (ref "U$19") (pin "+") (pinfunction "+_+") (pintype "bidirectional"))
    )
    (net (code "28") (name "Net-(R15-Pad1)") (class "Default")
      (node (ref "R15") (pin "1") (pinfunction "1_1") (pintype "passive"))
      (node (ref "U$3") (pin "TXD") (pinfunction "TXD_TXD") (pintype "bidirectional"))
    )
    (net (code "29") (name "Net-(R31-Pad1)") (class "Default")
      (node (ref "R31") (pin "1") (pinfunction "1_1") (pintype "passive"))
      (node (ref "R35") (pin "2") (pinfunction "2_2") (pintype "passive"))
      (node (ref "SV1") (pin "2") (pinfunction "2_2") (pintype "passive"))
    )
    (net (code "30") (name "Net-(R32-Pad1)") (class "Default")
      (node (ref "R32") (pin "1") (pinfunction "1_1") (pintype "passive"))
      (node (ref "R33") (pin "1") (pinfunction "1_1") (pintype "passive"))
      (node (ref "R34") (pin "2") (pinfunction "2_2") (pintype "passive"))
    )
    (net (code "31") (name "Net-(R33-Pad2)") (class "Default")
      (node (ref "R33") (pin "2") (pinfunction "2_2") (pintype "passive"))
      (node (ref "SV1") (pin "3") (pinfunction "3_3") (pintype "passive"))
    )
    (net (code "32") (name "Net-(U$1-PadL)") (class "Default")
      (node (ref "U$1") (pin "L") (pinfunction "L_L") (pintype "bidirectional"))
      (node (ref "U$20") (pin "L'") (pinfunction "L'_L'") (pintype "bidirectional"))
    )
    (net (code "33") (name "Net-(U$1-PadN)") (class "Default")
      (node (ref "U$1") (pin "N") (pinfunction "N_N") (pintype "bidirectional"))
      (node (ref "U$20") (pin "N'") (pinfunction "N'_N'") (pintype "bidirectional"))
    )
    (net (code "34") (name "Net-(U$4-LINE1)") (class "Default")
      (node (ref "U$4") (pin "P$20") (pinfunction "LINE1_P$20") (pintype "bidirectional"))
      (node (ref "U$5") (pin "1LINE1") (pinfunction "1OUT_1LINE1") (pintype "output"))
    )
    (net (code "35") (name "Net-(U$4-LINE2)") (class "Default")
      (node (ref "U$4") (pin "P$21") (pinfunction "LINE2_P$21") (pintype "bidirectional"))
      (node (ref "U$5") (pin "4LINE2") (pinfunction "4OUT_4LINE2") (pintype "output"))
    )
    (net (code "36") (name "Net-(U$4-NRESET)") (class "Default")
      (node (ref "C15") (pin "2") (pinfunction "2_2") (pintype "passive"))
      (node (ref "R6") (pin "2") (pinfunction "2_2") (pintype "passive"))
      (node (ref "U$4") (pin "P$9") (pinfunction "NRESET_P$9") (pintype "bidirectional"))
    )
    (net (code "37") (name "Net-(U$4-RXD)") (class "Default")
      (node (ref "R15") (pin "2") (pinfunction "2_2") (pintype "passive"))
      (node (ref "U$4") (pin "P$17") (pinfunction "RXD_P$17") (pintype "bidirectional"))
    )
    (net (code "38") (name "Net-(U$4-TXD)") (class "Default")
      (node (ref "U$3") (pin "RXD") (pinfunction "RXD_RXD") (pintype "bidirectional"))
      (node (ref "U$4") (pin "P$16") (pinfunction "TXD_P$16") (pintype "bidirectional"))
    )
    (net (code "39") (name "Net-(U$5-2OUT)") (class "Default")
      (node (ref "U$5") (pin "2") (pinfunction "2OUT_2") (pintype "output"))
      (node (ref "U$5") (pin "3") (pinfunction "3OUT_3") (pintype "output"))
    )
    (net (code "40") (name "Net-(U$5-5IN)") (class "Default")
      (node (ref "C2") (pin "2") (pinfunction "2_2") (pintype "passive"))
      (node (ref "C24") (pin "2") (pinfunction "2_2") (pintype "passive"))
      (node (ref "C25") (pin "2") (pinfunction "2_2") (pintype "passive"))
      (node (ref "R10") (pin "1") (pinfunction "1_1") (pintype "passive"))
      (node (ref "R4") (pin "1") (pinfunction "1_1") (pintype "passive"))
      (node (ref "R9") (pin "1") (pinfunction "1_1") (pintype "passive"))
      (node (ref "TSV2") (pin "P$1") (pinfunction "P$1_P$1") (pintype "bidirectional"))
      (node (ref "U$5") (pin "L5") (pinfunction "5IN_L5") (pintype "input"))
    )
    (net (code "41") (name "Net-(U$6-1)") (class "Default")
      (node (ref "C11") (pin "2") (pinfunction "2_2") (pintype "passive"))
      (node (ref "R16") (pin "2") (pinfunction "2_2") (pintype "passive"))
      (node (ref "U$6") (pin "P$1") (pinfunction "1_P$1") (pintype "output"))
    )
    (net (code "42") (name "Net-(U$7-1)") (class "Default")
      (node (ref "C13") (pin "2") (pinfunction "2_2") (pintype "passive"))
      (node (ref "R20") (pin "2") (pinfunction "2_2") (pintype "passive"))
      (node (ref "U$7") (pin "P$1") (pinfunction "1_P$1") (pintype "output"))
    )
    (net (code "43") (name "Net-(U$8-~{1})") (class "Default")
      (node (ref "U$2") (pin "OUT1") (pinfunction "OUT1_OUT1") (pintype "bidirectional"))
      (node (ref "U$8") (pin "~1") (pinfunction "~{1}_~1") (pintype "bidirectional"))
    )
    (net (code "44") (name "Net-(U$8-~{2})") (class "Default")
      (node (ref "U$2") (pin "OUT2") (pinfunction "OUT2_OUT2") (pintype "bidirectional"))
      (node (ref "U$8") (pin "~2") (pinfunction "~{2}_~2") (pintype "bidirectional"))
    )
    (net (code "45") (name "Net-(U$12-+VS)") (class "Default")
      (node (ref "C17") (pin "1") (pinfunction "1_1") (pintype "passive"))
      (node (ref "C18") (pin "2") (pinfunction "2_2") (pintype "passive"))
      (node (ref "R17") (pin "2") (pinfunction "2_2") (pintype "passive"))
      (node (ref "U$12") (pin "3") (pinfunction "+VS_3") (pintype "bidirectional"))
    )
    (net (code "46") (name "Net-(U$12-BUFIN)") (class "Default")
      (node (ref "U$12") (pin "10") (pinfunction "IOUT_10") (pintype "bidirectional"))
      (node (ref "U$12") (pin "9") (pinfunction "BUFIN_9") (pintype "bidirectional"))
    )
    (net (code "47") (name "Net-(U$12-CAV)") (class "Default")
      (node (ref "C17") (pin "2") (pinfunction "2_2") (pintype "passive"))
      (node (ref "U$12") (pin "6") (pinfunction "CAV_6") (pintype "bidirectional"))
    )
    (net (code "48") (name "Net-(U$12-COM)") (class "Default")
      (node (ref "C19") (pin "2") (pinfunction "2_2") (pintype "passive"))
      (node (ref "R17") (pin "1") (pinfunction "1_1") (pintype "passive"))
      (node (ref "R18") (pin "2") (pinfunction "2_2") (pintype "passive"))
      (node (ref "U$12") (pin "2") (pinfunction "COM_2") (pintype "bidirectional"))
    )
    (net (code "49") (name "Net-(U$12-VIN)") (class "Default")
      (node (ref "C13") (pin "1") (pinfunction "1_1") (pintype "passive"))
      (node (ref "U$12") (pin "4") (pinfunction "VIN_4") (pintype "bidirectional"))
    )
    (net (code "50") (name "Net-(U$13-+VS)") (class "Default")
      (node (ref "C12") (pin "1") (pinfunction "1_1") (pintype "passive"))
      (node (ref "C14") (pin "2") (pinfunction "2_2") (pintype "passive"))
      (node (ref "R3") (pin "2") (pinfunction "2_2") (pintype "passive"))
      (node (ref "U$13") (pin "3") (pinfunction "+VS_3") (pintype "bidirectional"))
    )
    (net (code "51") (name "Net-(U$13-BUFIN)") (class "Default")
      (node (ref "U$13") (pin "10") (pinfunction "IOUT_10") (pintype "bidirectional"))
      (node (ref "U$13") (pin "9") (pinfunction "BUFIN_9") (pintype "bidirectional"))
    )
    (net (code "52") (name "Net-(U$13-CAV)") (class "Default")
      (node (ref "C12") (pin "2") (pinfunction "2_2") (pintype "passive"))
      (node (ref "U$13") (pin "6") (pinfunction "CAV_6") (pintype "bidirectional"))
    )
    (net (code "53") (name "Net-(U$13-COM)") (class "Default")
      (node (ref "C16") (pin "2") (pinfunction "2_2") (pintype "passive"))
      (node (ref "R3") (pin "1") (pinfunction "1_1") (pintype "passive"))
      (node (ref "R7") (pin "2") (pinfunction "2_2") (pintype "passive"))
      (node (ref "U$13") (pin "2") (pinfunction "COM_2") (pintype "bidirectional"))
    )
    (net (code "54") (name "Net-(U$13-VIN)") (class "Default")
      (node (ref "C11") (pin "1") (pinfunction "1_1") (pintype "passive"))
      (node (ref "U$13") (pin "4") (pinfunction "VIN_4") (pintype "bidirectional"))
    )
    (net (code "55") (name "Net-(U$14-1)") (class "Default")
      (node (ref "C20") (pin "2") (pinfunction "2_2") (pintype "passive"))
      (node (ref "R24") (pin "2") (pinfunction "2_2") (pintype "passive"))
      (node (ref "U$14") (pin "P$1") (pinfunction "1_P$1") (pintype "output"))
    )
    (net (code "56") (name "Net-(U$15-+VS)") (class "Default")
      (node (ref "C21") (pin "1") (pinfunction "1_1") (pintype "passive"))
      (node (ref "C22") (pin "2") (pinfunction "2_2") (pintype "passive"))
      (node (ref "R21") (pin "2") (pinfunction "2_2") (pintype "passive"))
      (node (ref "U$15") (pin "3") (pinfunction "+VS_3") (pintype "bidirectional"))
    )
    (net (code "57") (name "Net-(U$15-BUFIN)") (class "Default")
      (node (ref "U$15") (pin "10") (pinfunction "IOUT_10") (pintype "bidirectional"))
      (node (ref "U$15") (pin "9") (pinfunction "BUFIN_9") (pintype "bidirectional"))
    )
    (net (code "58") (name "Net-(U$15-CAV)") (class "Default")
      (node (ref "C21") (pin "2") (pinfunction "2_2") (pintype "passive"))
      (node (ref "U$15") (pin "6") (pinfunction "CAV_6") (pintype "bidirectional"))
    )
    (net (code "59") (name "Net-(U$15-COM)") (class "Default")
      (node (ref "C23") (pin "2") (pinfunction "2_2") (pintype "passive"))
      (node (ref "R21") (pin "1") (pinfunction "1_1") (pintype "passive"))
      (node (ref "R22") (pin "2") (pinfunction "2_2") (pintype "passive"))
      (node (ref "U$15") (pin "2") (pinfunction "COM_2") (pintype "bidirectional"))
    )
    (net (code "60") (name "Net-(U$15-VIN)") (class "Default")
      (node (ref "C20") (pin "1") (pinfunction "1_1") (pintype "passive"))
      (node (ref "U$15") (pin "4") (pinfunction "VIN_4") (pintype "bidirectional"))
    )
    (net (code "61") (name "Net-(U$17-~{1})") (class "Default")
      (node (ref "U$16") (pin "OUT1") (pinfunction "OUT1_OUT1") (pintype "bidirectional"))
      (node (ref "U$17") (pin "~1") (pinfunction "~{1}_~1") (pintype "bidirectional"))
    )
    (net (code "62") (name "Net-(U$17-~{2})") (class "Default")
      (node (ref "U$16") (pin "OUT2") (pinfunction "OUT2_OUT2") (pintype "bidirectional"))
      (node (ref "U$17") (pin "~2") (pinfunction "~{2}_~2") (pintype "bidirectional"))
    )
    (net (code "63") (name "Net-(U$19-~{1})") (class "Default")
      (node (ref "U$18") (pin "OUT1") (pinfunction "OUT1_OUT1") (pintype "bidirectional"))
      (node (ref "U$19") (pin "~1") (pinfunction "~{1}_~1") (pintype "bidirectional"))
    )
    (net (code "64") (name "Net-(U$19-~{2})") (class "Default")
      (node (ref "U$18") (pin "OUT2") (pinfunction "OUT2_OUT2") (pintype "bidirectional"))
      (node (ref "U$19") (pin "~2") (pinfunction "~{2}_~2") (pintype "bidirectional"))
    )
    (net (code "65") (name "unconnected-(U$1-PadNC)") (class "Default")
      (node (ref "U$1") (pin "NC") (pinfunction "NC_NC") (pintype "bidirectional"))
    )
    (net (code "66") (name "unconnected-(U$1-PadNC1)") (class "Default")
      (node (ref "U$1") (pin "NC1") (pinfunction "NC1_NC1") (pintype "bidirectional"))
    )
    (net (code "67") (name "unconnected-(U$3-CLK-PadSCLOCK)") (class "Default")
      (node (ref "U$3") (pin "SCLOCK") (pinfunction "CLK_SCLOCK") (pintype "bidirectional"))
    )
    (net (code "68") (name "unconnected-(U$3-PadGND2)") (class "Default")
      (node (ref "U$3") (pin "GND2") (pinfunction "GND2_GND2") (pintype "bidirectional"))
    )
    (net (code "69") (name "unconnected-(U$3-PadGND3)") (class "Default")
      (node (ref "U$3") (pin "GND3") (pinfunction "GND3_GND3") (pintype "bidirectional"))
    )
    (net (code "70") (name "unconnected-(U$3-PadMISO)") (class "Default")
      (node (ref "U$3") (pin "MISO") (pinfunction "MISO_MISO") (pintype "bidirectional"))
    )
    (net (code "71") (name "unconnected-(U$3-PadMOSI)") (class "Default")
      (node (ref "U$3") (pin "MOSI") (pinfunction "MOSI_MOSI") (pintype "bidirectional"))
    )
    (net (code "72") (name "unconnected-(U$3-VCC2-PadVCC1)") (class "Default")
      (node (ref "U$3") (pin "VCC1") (pinfunction "VCC2_VCC1") (pintype "bidirectional"))
    )
    (net (code "73") (name "unconnected-(U$4-PadP$1)") (class "Default")
      (node (ref "U$4") (pin "P$1") (pinfunction "P$1_P$1") (pintype "bidirectional"))
    )
    (net (code "74") (name "unconnected-(U$4-PadP$6)") (class "Default")
      (node (ref "U$4") (pin "P$6") (pinfunction "P$6_P$6") (pintype "bidirectional"))
    )
    (net (code "75") (name "unconnected-(U$4-PadP$7)") (class "Default")
      (node (ref "U$4") (pin "P$7") (pinfunction "P$7_P$7") (pintype "bidirectional"))
    )
    (net (code "76") (name "unconnected-(U$4-PadP$8)") (class "Default")
      (node (ref "U$4") (pin "P$8") (pinfunction "P$8_P$8") (pintype "bidirectional"))
    )
    (net (code "77") (name "unconnected-(U$4-PadP$10)") (class "Default")
      (node (ref "U$4") (pin "P$10") (pinfunction "P$10_P$10") (pintype "bidirectional"))
    )
    (net (code "78") (name "unconnected-(U$4-PadP$11)") (class "Default")
      (node (ref "U$4") (pin "P$11") (pinfunction "P$11_P$11") (pintype "bidirectional"))
    )
    (net (code "79") (name "unconnected-(U$4-PadP$12)") (class "Default")
      (node (ref "U$4") (pin "P$12") (pinfunction "P$12_P$12") (pintype "bidirectional"))
    )
    (net (code "80") (name "unconnected-(U$4-PadP$13)") (class "Default")
      (node (ref "U$4") (pin "P$13") (pinfunction "P$13_P$13") (pintype "bidirectional"))
    )
    (net (code "81") (name "unconnected-(U$4-PadP$14)") (class "Default")
      (node (ref "U$4") (pin "P$14") (pinfunction "P$14_P$14") (pintype "bidirectional"))
    )
    (net (code "82") (name "unconnected-(U$4-PadP$15)") (class "Default")
      (node (ref "U$4") (pin "P$15") (pinfunction "P$15_P$15") (pintype "bidirectional"))
    )
    (net (code "83") (name "unconnected-(U$4-PadP$18)") (class "Default")
      (node (ref "U$4") (pin "P$18") (pinfunction "P$18_P$18") (pintype "bidirectional"))
    )
    (net (code "84") (name "unconnected-(U$4-PadP$19)") (class "Default")
      (node (ref "U$4") (pin "P$19") (pinfunction "P$19_P$19") (pintype "bidirectional"))
    )
    (net (code "85") (name "unconnected-(U$4-PadP$22)") (class "Default")
      (node (ref "U$4") (pin "P$22") (pinfunction "P$22_P$22") (pintype "bidirectional"))
    )
    (net (code "86") (name "unconnected-(U$4-PadP$23)") (class "Default")
      (node (ref "U$4") (pin "P$23") (pinfunction "P$23_P$23") (pintype "bidirectional"))
    )
    (net (code "87") (name "unconnected-(U$4-PadP$24)") (class "Default")
      (node (ref "U$4") (pin "P$24") (pinfunction "P$24_P$24") (pintype "bidirectional"))
    )
    (net (code "88") (name "unconnected-(U$4-PadP$26)") (class "Default")
      (node (ref "U$4") (pin "P$26") (pinfunction "P$26_P$26") (pintype "bidirectional"))
    )
    (net (code "89") (name "unconnected-(U$4-PadP$27)") (class "Default")
      (node (ref "U$4") (pin "P$27") (pinfunction "P$27_P$27") (pintype "bidirectional"))
    )
    (net (code "90") (name "unconnected-(U$4-PadP$28)") (class "Default")
      (node (ref "U$4") (pin "P$28") (pinfunction "P$28_P$28") (pintype "bidirectional"))
    )
    (net (code "91") (name "unconnected-(U$4-PadP$29)") (class "Default")
      (node (ref "U$4") (pin "P$29") (pinfunction "P$29_P$29") (pintype "bidirectional"))
    )
    (net (code "92") (name "unconnected-(U$4-PadP$30)") (class "Default")
      (node (ref "U$4") (pin "P$30") (pinfunction "P$30_P$30") (pintype "bidirectional"))
    )
    (net (code "93") (name "unconnected-(U$4-PadP$31)") (class "Default")
      (node (ref "U$4") (pin "P$31") (pinfunction "P$31_P$31") (pintype "bidirectional"))
    )
    (net (code "94") (name "unconnected-(U$6-3-PadP$3)") (class "Default")
      (node (ref "U$6") (pin "P$3") (pinfunction "3_P$3") (pintype "no_connect"))
    )
    (net (code "95") (name "unconnected-(U$7-3-PadP$3)") (class "Default")
      (node (ref "U$7") (pin "P$3") (pinfunction "3_P$3") (pintype "no_connect"))
    )
    (net (code "96") (name "unconnected-(U$12-DB-Pad7)") (class "Default")
      (node (ref "U$12") (pin "7") (pinfunction "DB_7") (pintype "bidirectional"))
    )
    (net (code "97") (name "unconnected-(U$12-RL-Pad1)") (class "Default")
      (node (ref "U$12") (pin "1") (pinfunction "RL_1") (pintype "bidirectional"))
    )
    (net (code "98") (name "unconnected-(U$13-DB-Pad7)") (class "Default")
      (node (ref "U$13") (pin "7") (pinfunction "DB_7") (pintype "bidirectional"))
    )
    (net (code "99") (name "unconnected-(U$13-RL-Pad1)") (class "Default")
      (node (ref "U$13") (pin "1") (pinfunction "RL_1") (pintype "bidirectional"))
    )
    (net (code "100") (name "unconnected-(U$14-3-PadP$3)") (class "Default")
      (node (ref "U$14") (pin "P$3") (pinfunction "3_P$3") (pintype "no_connect"))
    )
    (net (code "101") (name "unconnected-(U$15-DB-Pad7)") (class "Default")
      (node (ref "U$15") (pin "7") (pinfunction "DB_7") (pintype "bidirectional"))
    )
    (net (code "102") (name "unconnected-(U$15-RL-Pad1)") (class "Default")
      (node (ref "U$15") (pin "1") (pinfunction "RL_1") (pintype "bidirectional"))
    )
  )
)
